# 2014_FDP_Generic_Port_Act.net
KiCad netlist of a schematic drawn in Altium Designer
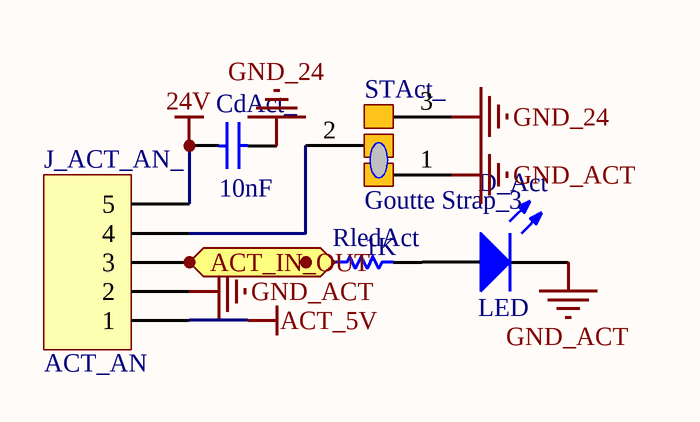
[diagram p0: 2014_FDP_Generic_Port_Act.SchDoc]

(export (version "E")
  (design (tool "Eeschema 10.0.6"))
  (components
    (comp (ref "CdAct_")
      (value "10nF")
      (footprint "C0805_N")
      (description "Capacitor")
      (fields (field (name "PUBLISHER") "Altium Limited"))
      (libsource (lib "_ROBOT") (part "Condensateur"))
    )
    (comp (ref "D_Act")
      (value "LED")
      (footprint "LED_0805")
      (description "Typical LED")
      (fields (field (name "PUBLISHER") "Altium Limited"))
      (libsource (lib "_ROBOT") (part "LED"))
    )
    (comp (ref "J_ACT_AN_")
      (value "ACT_AN")
      (footprint "HE14_5")
      (description "Header, 5-Pin")
      (fields (field (name "PUBLISHER") "Altium Limited"))
      (libsource (lib "Connecteur") (part "BARRETTE5"))
    )
    (comp (ref "RledAct")
      (value "1K")
      (footprint "R1206_N")
      (description "Resistor")
      (fields (field (name "PUBLISHER") "Altium Limited"))
      (libsource (lib "_ROBOT") (part "Resistor"))
    )
    (comp (ref "STAct_")
      (value "Goutte Strap_3")
      (footprint "Goutte Strap_3")
      (fields (field (name "PUBLISHER") "Damien Guitton"))
      (libsource (lib "DG_Connecteur") (part "Goutte Strap_3"))
    )
  )
  (nets
    (net (code "1") (name "/ACT_IN_OUT") (class "Default")
      (node (ref "J_ACT_AN_") (pin "3") (pinfunction "3_3") (pintype "passive"))
      (node (ref "RledAct") (pin "1") (pinfunction "1_1") (pintype "passive"))
    )
    (net (code "2") (name "24V") (class "Default")
      (node (ref "CdAct_") (pin "1") (pinfunction "1_1") (pintype "passive"))
      (node (ref "J_ACT_AN_") (pin "5") (pinfunction "5_5") (pintype "passive"))
    )
    (net (code "3") (name "ACT_5V") (class "Default")
      (node (ref "J_ACT_AN_") (pin "1") (pinfunction "1_1") (pintype "passive"))
    )
    (net (code "4") (name "GND_24") (class "Default")
      (node (ref "CdAct_") (pin "2") (pinfunction "2_2") (pintype "passive"))
      (node (ref "STAct_") (pin "3") (pinfunction "3_3") (pintype "passive"))
    )
    (net (code "5") (name "GND_ACT") (class "Default")
      (node (ref "D_Act") (pin "2") (pinfunction "K_2") (pintype "passive"))
      (node (ref "J_ACT_AN_") (pin "2") (pinfunction "2_2") (pintype "passive"))
      (node (ref "STAct_") (pin "1") (pinfunction "1_1") (pintype "passive"))
    )
    (net (code "6") (name "Net-(D_Act-A)") (class "Default")
      (node (ref "D_Act") (pin "1") (pinfunction "A_1") (pintype "passive"))
      (node (ref "RledAct") (pin "2") (pinfunction "2_2") (pintype "passive"))
    )
    (net (code "7") (name "Net-(J_ACT_AN_-Pad4)") (class "Default")
      (node (ref "J_ACT_AN_") (pin "4") (pinfunction "4_4") (pintype "passive"))
      (node (ref "STAct_") (pin "2") (pinfunction "2_2") (pintype "passive"))
    )
  )
)
